# 04_DRIVER.net
KiCad netlist of a schematic drawn in Altium Designer
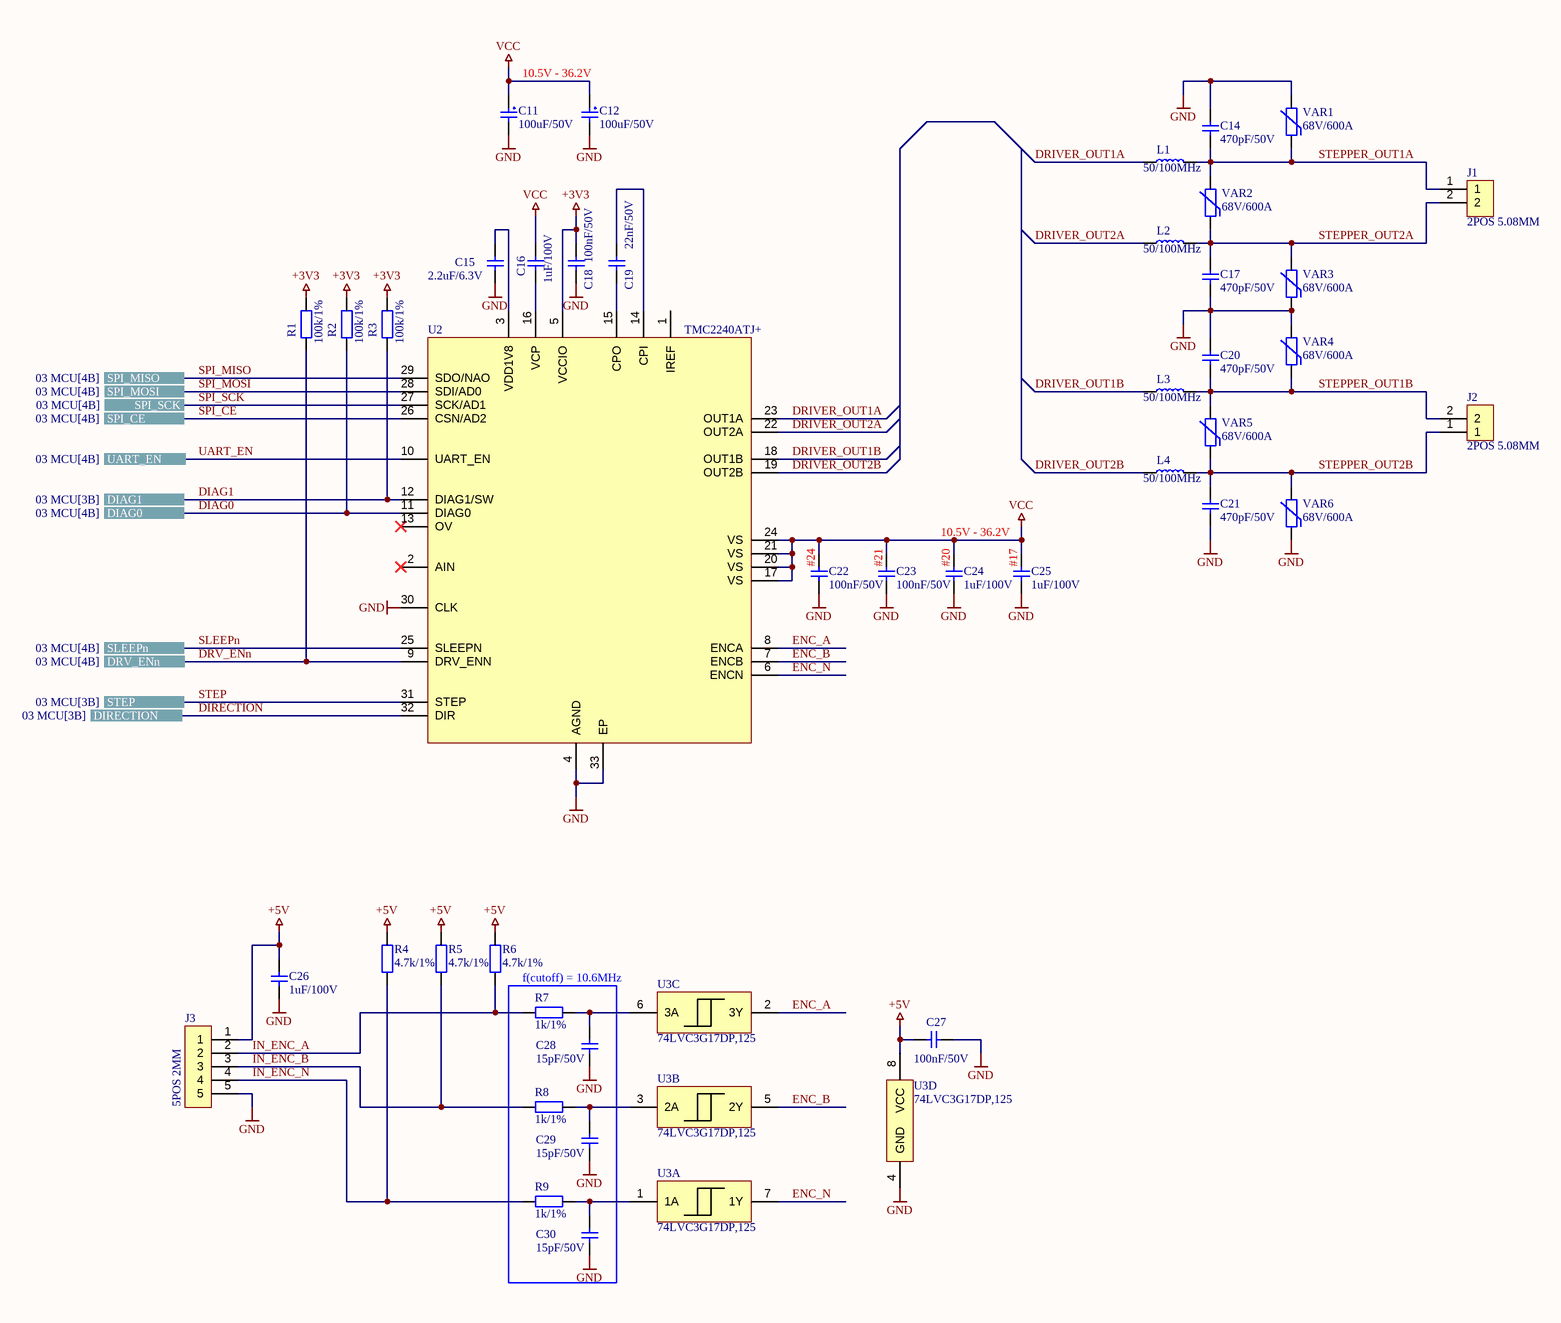
[diagram p0: 04 DRIVER.SchDoc]

(export (version "E")
  (design (tool "Eeschema 10.0.6"))
  (components
    (comp (ref "C11")
      (value "100uF/50V")
      (footprint "A768KS107M1HLAE030")
      (description "100 µF 50 V Aluminum - Polymer Capacitors Radial, Can - SMD 30mOhm 2000 Hrs @ 125°C")
      (fields (field (name "MPN") "A768KS107M1HLAE030"))
      (libsource (lib "Symbol") (part "A768KS107M1HLAE030"))
    )
    (comp (ref "C12")
      (value "100uF/50V")
      (footprint "A768KS107M1HLAE030")
      (description "100 µF 50 V Aluminum - Polymer Capacitors Radial, Can - SMD 30mOhm 2000 Hrs @ 125°C")
      (fields (field (name "MPN") "A768KS107M1HLAE030"))
      (libsource (lib "Symbol") (part "A768KS107M1HLAE030"))
    )
    (comp (ref "C14")
      (value "470pF/50V")
      (footprint "CAPC1005X06M-0402")
      (description "470 pF ±10% 50V Ceramic Capacitor X7R 0402 (1005 Metric)")
      (fields (field (name "MPN") "GRM155R71H471KA01D"))
      (libsource (lib "Symbol") (part "GRM155R71H471KA01D"))
    )
    (comp (ref "C15")
      (value "2.2uF/6.3V")
      (footprint "CAPC1005X06M-0402")
      (description "2.2 µF ±10% 6.3V Ceramic Capacitor X6S 0402 (1005 Metric)")
      (fields (field (name "MPN") "GRM155C80J225KE95D"))
      (libsource (lib "Symbol") (part "GRM155C80J225KE95D"))
    )
    (comp (ref "C16")
      (value "1uF/100V")
      (footprint "CAPC2012X14M")
      (description "1 µF ±10% 100V Ceramic Capacitor X7S 0805 (2012 Metric)")
      (fields (field (name "MPN") "GRM21BC72A105KE01L"))
      (libsource (lib "Symbol") (part "GRM21BC72A105KE01L"))
    )
    (comp (ref "C17")
      (value "470pF/50V")
      (footprint "CAPC1005X06M-0402")
      (description "470 pF ±10% 50V Ceramic Capacitor X7R 0402 (1005 Metric)")
      (fields (field (name "MPN") "GRM155R71H471KA01D"))
      (libsource (lib "Symbol") (part "GRM155R71H471KA01D"))
    )
    (comp (ref "C18")
      (value "100nF/50V")
      (footprint "CAPC1005X06M-0402")
      (description "0.1 µF ±10% 50V Ceramic Capacitor X7R 0402 (1005 Metric)")
      (fields (field (name "MPN") "GRM155R71H104KE14D"))
      (libsource (lib "Symbol") (part "GRM155R71H104KE14D"))
    )
    (comp (ref "C19")
      (value "22nF/50V")
      (footprint "CAPC1005X06M-0402")
      (description "0.022 µF ±10% 50V Ceramic Capacitor X7R 0402 (1005 Metric)")
      (fields (field (name "MPN") "GRM155R71H223KA12D"))
      (libsource (lib "Symbol") (part "GRM155R71H223KA12D"))
    )
    (comp (ref "C20")
      (value "470pF/50V")
      (footprint "CAPC1005X06M-0402")
      (description "470 pF ±10% 50V Ceramic Capacitor X7R 0402 (1005 Metric)")
      (fields (field (name "MPN") "GRM155R71H471KA01D"))
      (libsource (lib "Symbol") (part "GRM155R71H471KA01D"))
    )
    (comp (ref "C21")
      (value "470pF/50V")
      (footprint "CAPC1005X06M-0402")
      (description "470 pF ±10% 50V Ceramic Capacitor X7R 0402 (1005 Metric)")
      (fields (field (name "MPN") "GRM155R71H471KA01D"))
      (libsource (lib "Symbol") (part "GRM155R71H471KA01D"))
    )
    (comp (ref "C22")
      (value "100nF/50V")
      (footprint "CAPC1005X06M-0402")
      (description "0.1 µF ±10% 50V Ceramic Capacitor X7R 0402 (1005 Metric)")
      (fields (field (name "MPN") "GRM155R71H104KE14D"))
      (libsource (lib "Symbol") (part "GRM155R71H104KE14D"))
    )
    (comp (ref "C23")
      (value "100nF/50V")
      (footprint "CAPC1005X06M-0402")
      (description "0.1 µF ±10% 50V Ceramic Capacitor X7R 0402 (1005 Metric)")
      (fields (field (name "MPN") "GRM155R71H104KE14D"))
      (libsource (lib "Symbol") (part "GRM155R71H104KE14D"))
    )
    (comp (ref "C24")
      (value "1uF/100V")
      (footprint "CAPC2012X14M")
      (description "1 µF ±10% 100V Ceramic Capacitor X7S 0805 (2012 Metric)")
      (fields (field (name "MPN") "GRM21BC72A105KE01L"))
      (libsource (lib "Symbol") (part "GRM21BC72A105KE01L"))
    )
    (comp (ref "C25")
      (value "1uF/100V")
      (footprint "CAPC2012X14M")
      (description "1 µF ±10% 100V Ceramic Capacitor X7S 0805 (2012 Metric)")
      (fields (field (name "MPN") "GRM21BC72A105KE01L"))
      (libsource (lib "Symbol") (part "GRM21BC72A105KE01L"))
    )
    (comp (ref "C26")
      (value "1uF/100V")
      (footprint "CAPC2012X14M")
      (description "1 µF ±10% 100V Ceramic Capacitor X7S 0805 (2012 Metric)")
      (fields (field (name "MPN") "GRM21BC72A105KE01L"))
      (libsource (lib "Symbol") (part "GRM21BC72A105KE01L"))
    )
    (comp (ref "C27")
      (value "100nF/50V")
      (footprint "CAPC1005X06M-0402")
      (description "0.1 µF ±10% 50V Ceramic Capacitor X7R 0402 (1005 Metric)")
      (fields (field (name "MPN") "GRM155R71H104KE14D"))
      (libsource (lib "Symbol") (part "GRM155R71H104KE14D"))
    )
    (comp (ref "C28")
      (value "15pF/50V")
      (footprint "CAPC1005X06M-0402")
      (description "15 pF ±5% 50V Ceramic Capacitor C0G, NP0 0402 (1005 Metric)")
      (fields (field (name "MPN") "GRM1555C1H150JA01D"))
      (libsource (lib "Symbol") (part "GRM1555C1H150JA01D"))
    )
    (comp (ref "C29")
      (value "15pF/50V")
      (footprint "CAPC1005X06M-0402")
      (description "15 pF ±5% 50V Ceramic Capacitor C0G, NP0 0402 (1005 Metric)")
      (fields (field (name "MPN") "GRM1555C1H150JA01D"))
      (libsource (lib "Symbol") (part "GRM1555C1H150JA01D"))
    )
    (comp (ref "C30")
      (value "15pF/50V")
      (footprint "CAPC1005X06M-0402")
      (description "15 pF ±5% 50V Ceramic Capacitor C0G, NP0 0402 (1005 Metric)")
      (fields (field (name "MPN") "GRM1555C1H150JA01D"))
      (libsource (lib "Symbol") (part "GRM1555C1H150JA01D"))
    )
    (comp (ref "J1")
      (value "2POS 5.08MM")
      (footprint "282837-2")
      (fields (field (name "MPN") "282834-3"))
      (libsource (lib "") (part "282837-2_1"))
    )
    (comp (ref "J2")
      (value "2POS 5.08MM")
      (footprint "282837-2")
      (fields (field (name "MPN") "282834-3"))
      (libsource (lib "Symbol") (part "282837-2"))
    )
    (comp (ref "J3")
      (value "5POS 2MM")
      (footprint "B5B-PH-K-S")
      (description "Connector Header Through Hole 5 position 0.079\" (2.00mm)")
      (fields (field (name "MPN") "B5B-PH-K-S"))
      (libsource (lib "Symbol") (part "B5B-PH-K-S"))
    )
    (comp (ref "L1")
      (value "50/100MHz")
      (footprint "INDC3200X110-1206")
      (description "50 Ohms 1 Signal Line Ferrite Bead 1206 (3216 Metric) 3A 25mOhm")
      (fields (field (name "MPN") "742792114"))
      (libsource (lib "Symbol") (part "742792114"))
    )
    (comp (ref "L2")
      (value "50/100MHz")
      (footprint "INDC3200X110-1206")
      (description "50 Ohms 1 Signal Line Ferrite Bead 1206 (3216 Metric) 3A 25mOhm")
      (fields (field (name "MPN") "742792114"))
      (libsource (lib "Symbol") (part "742792114"))
    )
    (comp (ref "L3")
      (value "50/100MHz")
      (footprint "INDC3200X110-1206")
      (description "50 Ohms 1 Signal Line Ferrite Bead 1206 (3216 Metric) 3A 25mOhm")
      (fields (field (name "MPN") "742792114"))
      (libsource (lib "Symbol") (part "742792114"))
    )
    (comp (ref "L4")
      (value "50/100MHz")
      (footprint "INDC3200X110-1206")
      (description "50 Ohms 1 Signal Line Ferrite Bead 1206 (3216 Metric) 3A 25mOhm")
      (fields (field (name "MPN") "742792114"))
      (libsource (lib "Symbol") (part "742792114"))
    )
    (comp (ref "R1")
      (value "100k/1%")
      (footprint "RESC1005X04M-0402")
      (description "100 kOhms ±1% 0.063W, 1/16W Chip Resistor 0402 (1005 Metric) Moisture Resistant Thick Film")
      (fields (field (name "MPN") "RC0402FR-07100KL"))
      (libsource (lib "Symbol") (part "RC0402FR-07100KL"))
    )
    (comp (ref "R2")
      (value "100k/1%")
      (footprint "RESC1005X04M-0402")
      (description "100 kOhms ±1% 0.063W, 1/16W Chip Resistor 0402 (1005 Metric) Moisture Resistant Thick Film")
      (fields (field (name "MPN") "RC0402FR-07100KL"))
      (libsource (lib "Symbol") (part "RC0402FR-07100KL"))
    )
    (comp (ref "R3")
      (value "100k/1%")
      (footprint "RESC1005X04M-0402")
      (description "100 kOhms ±1% 0.063W, 1/16W Chip Resistor 0402 (1005 Metric) Moisture Resistant Thick Film")
      (fields (field (name "MPN") "RC0402FR-07100KL"))
      (libsource (lib "Symbol") (part "RC0402FR-07100KL"))
    )
    (comp (ref "R4")
      (value "4.7k/1%")
      (footprint "RESC1005X04M-0402")
      (description "4.7 kOhms ±1% 0.063W, 1/16W Chip Resistor 0402 (1005 Metric) Moisture Resistant Thick Film")
      (fields (field (name "MPN") "RC0402FR-074K7L"))
      (libsource (lib "Symbol") (part "RC0402FR-074K7L"))
    )
    (comp (ref "R5")
      (value "4.7k/1%")
      (footprint "RESC1005X04M-0402")
      (description "4.7 kOhms ±1% 0.063W, 1/16W Chip Resistor 0402 (1005 Metric) Moisture Resistant Thick Film")
      (fields (field (name "MPN") "RC0402FR-074K7L"))
      (libsource (lib "Symbol") (part "RC0402FR-074K7L"))
    )
    (comp (ref "R6")
      (value "4.7k/1%")
      (footprint "RESC1005X04M-0402")
      (description "4.7 kOhms ±1% 0.063W, 1/16W Chip Resistor 0402 (1005 Metric) Moisture Resistant Thick Film")
      (fields (field (name "MPN") "RC0402FR-074K7L"))
      (libsource (lib "Symbol") (part "RC0402FR-074K7L"))
    )
    (comp (ref "R7")
      (value "1k/1%")
      (footprint "RESC1005X04M-0402")
      (description "1 kOhms ±1% 0.063W, 1/16W Chip Resistor 0402 (1005 Metric) Moisture Resistant Thick Film")
      (fields (field (name "MPN") "RC0402FR-071KL"))
      (libsource (lib "Symbol") (part "RC0402FR-071KL"))
    )
    (comp (ref "R8")
      (value "1k/1%")
      (footprint "RESC1005X04M-0402")
      (description "1 kOhms ±1% 0.063W, 1/16W Chip Resistor 0402 (1005 Metric) Moisture Resistant Thick Film")
      (fields (field (name "MPN") "RC0402FR-071KL"))
      (libsource (lib "Symbol") (part "RC0402FR-071KL"))
    )
    (comp (ref "R9")
      (value "1k/1%")
      (footprint "RESC1005X04M-0402")
      (description "1 kOhms ±1% 0.063W, 1/16W Chip Resistor 0402 (1005 Metric) Moisture Resistant Thick Film")
      (fields (field (name "MPN") "RC0402FR-071KL"))
      (libsource (lib "Symbol") (part "RC0402FR-071KL"))
    )
    (comp (ref "U2")
      (value "TMC2240ATJ+")
      (footprint "TQFN32-5mmx5mm")
      (description "Bipolar Motor Driver Power MOSFET SPI, UART 32-TQFN-EP (5x5)")
      (libsource (lib "Symbol") (part "TMC2240ATJ+"))
    )
    (comp (ref "U3")
      (value "74LVC3G17DP,125")
      (footprint "TSOP65P400X110-8N")
      (description "Buffer, Non-Inverting 3 Element 1 Bit per Element Push-Pull Output 8-TSSOP")
      (libsource (lib "Symbol") (part "74LVC3G17DP,125"))
    )
    (comp (ref "VAR1")
      (value "68V/600A")
      (footprint "VARA4732X16N")
      (description "68 V 600 A Varistor 1 Circuit Surface Mount, MLCV 1812 (4532 Metric)")
      (fields (field (name "MPN") "ZV40K1812601NIR1"))
      (libsource (lib "Symbol") (part "ZV40K1812601NIR1"))
    )
    (comp (ref "VAR2")
      (value "68V/600A")
      (footprint "VARA4732X16N")
      (description "68 V 600 A Varistor 1 Circuit Surface Mount, MLCV 1812 (4532 Metric)")
      (fields (field (name "MPN") "ZV40K1812601NIR1"))
      (libsource (lib "Symbol") (part "ZV40K1812601NIR1"))
    )
    (comp (ref "VAR3")
      (value "68V/600A")
      (footprint "VARA4732X16N")
      (description "68 V 600 A Varistor 1 Circuit Surface Mount, MLCV 1812 (4532 Metric)")
      (fields (field (name "MPN") "ZV40K1812601NIR1"))
      (libsource (lib "Symbol") (part "ZV40K1812601NIR1"))
    )
    (comp (ref "VAR4")
      (value "68V/600A")
      (footprint "VARA4732X16N")
      (description "68 V 600 A Varistor 1 Circuit Surface Mount, MLCV 1812 (4532 Metric)")
      (fields (field (name "MPN") "ZV40K1812601NIR1"))
      (libsource (lib "Symbol") (part "ZV40K1812601NIR1"))
    )
    (comp (ref "VAR5")
      (value "68V/600A")
      (footprint "VARA4732X16N")
      (description "68 V 600 A Varistor 1 Circuit Surface Mount, MLCV 1812 (4532 Metric)")
      (fields (field (name "MPN") "ZV40K1812601NIR1"))
      (libsource (lib "Symbol") (part "ZV40K1812601NIR1"))
    )
    (comp (ref "VAR6")
      (value "68V/600A")
      (footprint "VARA4732X16N")
      (description "68 V 600 A Varistor 1 Circuit Surface Mount, MLCV 1812 (4532 Metric)")
      (fields (field (name "MPN") "ZV40K1812601NIR1"))
      (libsource (lib "Symbol") (part "ZV40K1812601NIR1"))
    )
  )
  (nets
    (net (code "1") (name "+3V3") (class "Default")
      (node (ref "C18") (pin "2") (pinfunction "2_2") (pintype "passive"))
      (node (ref "R1") (pin "2") (pinfunction "2_2") (pintype "passive"))
      (node (ref "R2") (pin "2") (pinfunction "2_2") (pintype "passive"))
      (node (ref "R3") (pin "2") (pinfunction "2_2") (pintype "passive"))
      (node (ref "U2") (pin "5") (pinfunction "VCCIO_5") (pintype "power_in"))
    )
    (net (code "2") (name "+5V") (class "Default")
      (node (ref "C26") (pin "2") (pinfunction "2_2") (pintype "passive"))
      (node (ref "C27") (pin "1") (pinfunction "1_1") (pintype "passive"))
      (node (ref "J3") (pin "1") (pinfunction "1_1") (pintype "passive"))
      (node (ref "R4") (pin "2") (pinfunction "2_2") (pintype "passive"))
      (node (ref "R5") (pin "2") (pinfunction "2_2") (pintype "passive"))
      (node (ref "R6") (pin "2") (pinfunction "2_2") (pintype "passive"))
      (node (ref "U3") (pin "8") (pinfunction "VCC_8") (pintype "passive"))
    )
    (net (code "3") (name "/DIAG0") (class "Default")
      (node (ref "R2") (pin "1") (pinfunction "1_1") (pintype "passive"))
      (node (ref "U2") (pin "11") (pinfunction "DIAG0_11") (pintype "passive"))
    )
    (net (code "4") (name "/DIAG1") (class "Default")
      (node (ref "R3") (pin "1") (pinfunction "1_1") (pintype "passive"))
      (node (ref "U2") (pin "12") (pinfunction "DIAG1/SW_12") (pintype "passive"))
    )
    (net (code "5") (name "/DIRECTION") (class "Default")
      (node (ref "U2") (pin "32") (pinfunction "DIR_32") (pintype "passive"))
    )
    (net (code "6") (name "/DRIVER_OUT1A") (class "Default")
      (node (ref "L1") (pin "1") (pinfunction "1_1") (pintype "passive"))
      (node (ref "U2") (pin "23") (pinfunction "OUT1A_23") (pintype "passive"))
    )
    (net (code "7") (name "/DRIVER_OUT1B") (class "Default")
      (node (ref "L3") (pin "1") (pinfunction "1_1") (pintype "passive"))
      (node (ref "U2") (pin "18") (pinfunction "OUT1B_18") (pintype "passive"))
    )
    (net (code "8") (name "/DRIVER_OUT2A") (class "Default")
      (node (ref "L2") (pin "1") (pinfunction "1_1") (pintype "passive"))
      (node (ref "U2") (pin "22") (pinfunction "OUT2A_22") (pintype "passive"))
    )
    (net (code "9") (name "/DRIVER_OUT2B") (class "Default")
      (node (ref "L4") (pin "1") (pinfunction "1_1") (pintype "passive"))
      (node (ref "U2") (pin "19") (pinfunction "OUT2B_19") (pintype "passive"))
    )
    (net (code "10") (name "/DRV_ENn") (class "Default")
      (node (ref "R1") (pin "1") (pinfunction "1_1") (pintype "passive"))
      (node (ref "U2") (pin "9") (pinfunction "DRV_ENN_9") (pintype "passive"))
    )
    (net (code "11") (name "/ENC_A") (class "Default")
      (node (ref "U2") (pin "8") (pinfunction "ENCA_8") (pintype "passive"))
      (node (ref "U3") (pin "2") (pinfunction "3Y_2") (pintype "passive"))
    )
    (net (code "12") (name "/ENC_B") (class "Default")
      (node (ref "U2") (pin "7") (pinfunction "ENCB_7") (pintype "passive"))
      (node (ref "U3") (pin "5") (pinfunction "2Y_5") (pintype "passive"))
    )
    (net (code "13") (name "/ENC_N") (class "Default")
      (node (ref "U2") (pin "6") (pinfunction "ENCN_6") (pintype "passive"))
      (node (ref "U3") (pin "7") (pinfunction "1Y_7") (pintype "passive"))
    )
    (net (code "14") (name "/IN_ENC_A") (class "Default")
      (node (ref "J3") (pin "2") (pinfunction "2_2") (pintype "passive"))
      (node (ref "R6") (pin "1") (pinfunction "1_1") (pintype "passive"))
      (node (ref "R7") (pin "1") (pinfunction "1_1") (pintype "passive"))
    )
    (net (code "15") (name "/IN_ENC_B") (class "Default")
      (node (ref "J3") (pin "3") (pinfunction "3_3") (pintype "passive"))
      (node (ref "R5") (pin "1") (pinfunction "1_1") (pintype "passive"))
      (node (ref "R8") (pin "1") (pinfunction "1_1") (pintype "passive"))
    )
    (net (code "16") (name "/IN_ENC_N") (class "Default")
      (node (ref "J3") (pin "4") (pinfunction "4_4") (pintype "passive"))
      (node (ref "R4") (pin "1") (pinfunction "1_1") (pintype "passive"))
      (node (ref "R9") (pin "1") (pinfunction "1_1") (pintype "passive"))
    )
    (net (code "17") (name "/SLEEPn") (class "Default")
      (node (ref "U2") (pin "25") (pinfunction "SLEEPN_25") (pintype "passive"))
    )
    (net (code "18") (name "/SPI_CE") (class "Default")
      (node (ref "U2") (pin "26") (pinfunction "CSN/AD2_26") (pintype "passive"))
    )
    (net (code "19") (name "/SPI_MISO") (class "Default")
      (node (ref "U2") (pin "29") (pinfunction "SDO/NAO_29") (pintype "passive"))
    )
    (net (code "20") (name "/SPI_MOSI") (class "Default")
      (node (ref "U2") (pin "28") (pinfunction "SDI/AD0_28") (pintype "passive"))
    )
    (net (code "21") (name "/SPI_SCK") (class "Default")
      (node (ref "U2") (pin "27") (pinfunction "SCK/AD1_27") (pintype "passive"))
    )
    (net (code "22") (name "/STEP") (class "Default")
      (node (ref "U2") (pin "31") (pinfunction "STEP_31") (pintype "passive"))
    )
    (net (code "23") (name "/STEPPER_OUT1A") (class "Default")
      (node (ref "C14") (pin "2") (pinfunction "2_2") (pintype "passive"))
      (node (ref "J1") (pin "1") (pinfunction "1_1") (pintype "passive"))
      (node (ref "L1") (pin "2") (pinfunction "2_2") (pintype "passive"))
      (node (ref "VAR1") (pin "1") (pinfunction "1_1") (pintype "passive"))
      (node (ref "VAR2") (pin "2") (pinfunction "2_2") (pintype "passive"))
    )
    (net (code "24") (name "/STEPPER_OUT1B") (class "Default")
      (node (ref "C20") (pin "2") (pinfunction "2_2") (pintype "passive"))
      (node (ref "J2") (pin "2") (pinfunction "2_2") (pintype "passive"))
      (node (ref "L3") (pin "2") (pinfunction "2_2") (pintype "passive"))
      (node (ref "VAR4") (pin "1") (pinfunction "1_1") (pintype "passive"))
      (node (ref "VAR5") (pin "2") (pinfunction "2_2") (pintype "passive"))
    )
    (net (code "25") (name "/STEPPER_OUT2A") (class "Default")
      (node (ref "C17") (pin "1") (pinfunction "1_1") (pintype "passive"))
      (node (ref "J1") (pin "2") (pinfunction "2_2") (pintype "passive"))
      (node (ref "L2") (pin "2") (pinfunction "2_2") (pintype "passive"))
      (node (ref "VAR2") (pin "1") (pinfunction "1_1") (pintype "passive"))
      (node (ref "VAR3") (pin "2") (pinfunction "2_2") (pintype "passive"))
    )
    (net (code "26") (name "/STEPPER_OUT2B") (class "Default")
      (node (ref "C21") (pin "1") (pinfunction "1_1") (pintype "passive"))
      (node (ref "J2") (pin "1") (pinfunction "1_1") (pintype "passive"))
      (node (ref "L4") (pin "2") (pinfunction "2_2") (pintype "passive"))
      (node (ref "VAR5") (pin "1") (pinfunction "1_1") (pintype "passive"))
      (node (ref "VAR6") (pin "2") (pinfunction "2_2") (pintype "passive"))
    )
    (net (code "27") (name "/UART_EN") (class "Default")
      (node (ref "U2") (pin "10") (pinfunction "UART_EN_10") (pintype "passive"))
    )
    (net (code "28") (name "GND") (class "Default")
      (node (ref "C11") (pin "2") (pinfunction "2_2") (pintype "passive"))
      (node (ref "C12") (pin "2") (pinfunction "2_2") (pintype "passive"))
      (node (ref "C14") (pin "1") (pinfunction "1_1") (pintype "passive"))
      (node (ref "C15") (pin "1") (pinfunction "1_1") (pintype "passive"))
      (node (ref "C17") (pin "2") (pinfunction "2_2") (pintype "passive"))
      (node (ref "C18") (pin "1") (pinfunction "1_1") (pintype "passive"))
      (node (ref "C20") (pin "1") (pinfunction "1_1") (pintype "passive"))
      (node (ref "C21") (pin "2") (pinfunction "2_2") (pintype "passive"))
      (node (ref "C22") (pin "1") (pinfunction "1_1") (pintype "passive"))
      (node (ref "C23") (pin "1") (pinfunction "1_1") (pintype "passive"))
      (node (ref "C24") (pin "1") (pinfunction "1_1") (pintype "passive"))
      (node (ref "C25") (pin "1") (pinfunction "1_1") (pintype "passive"))
      (node (ref "C26") (pin "1") (pinfunction "1_1") (pintype "passive"))
      (node (ref "C27") (pin "2") (pinfunction "2_2") (pintype "passive"))
      (node (ref "C28") (pin "1") (pinfunction "1_1") (pintype "passive"))
      (node (ref "C29") (pin "1") (pinfunction "1_1") (pintype "passive"))
      (node (ref "C30") (pin "1") (pinfunction "1_1") (pintype "passive"))
      (node (ref "J3") (pin "5") (pinfunction "5_5") (pintype "passive"))
      (node (ref "U2") (pin "30") (pinfunction "CLK_30") (pintype "passive"))
      (node (ref "U2") (pin "33") (pinfunction "EP_33") (pintype "passive"))
      (node (ref "U2") (pin "4") (pinfunction "AGND_4") (pintype "power_in"))
      (node (ref "U3") (pin "4") (pinfunction "GND_4") (pintype "passive"))
      (node (ref "VAR1") (pin "2") (pinfunction "2_2") (pintype "passive"))
      (node (ref "VAR3") (pin "1") (pinfunction "1_1") (pintype "passive"))
      (node (ref "VAR4") (pin "2") (pinfunction "2_2") (pintype "passive"))
      (node (ref "VAR6") (pin "1") (pinfunction "1_1") (pintype "passive"))
    )
    (net (code "29") (name "Net-(U2-CPI)") (class "Default")
      (node (ref "C19") (pin "2") (pinfunction "2_2") (pintype "passive"))
      (node (ref "U2") (pin "14") (pinfunction "CPI_14") (pintype "passive"))
    )
    (net (code "30") (name "Net-(U2-CPO)") (class "Default")
      (node (ref "C19") (pin "1") (pinfunction "1_1") (pintype "passive"))
      (node (ref "U2") (pin "15") (pinfunction "CPO_15") (pintype "passive"))
    )
    (net (code "31") (name "Net-(U2-VCP)") (class "Default")
      (node (ref "C16") (pin "1") (pinfunction "1_1") (pintype "passive"))
      (node (ref "U2") (pin "16") (pinfunction "VCP_16") (pintype "power_in"))
    )
    (net (code "32") (name "Net-(U2-VDD1V8)") (class "Default")
      (node (ref "C15") (pin "2") (pinfunction "2_2") (pintype "passive"))
      (node (ref "U2") (pin "3") (pinfunction "VDD1V8_3") (pintype "power_in"))
    )
    (net (code "33") (name "Net-(U3A-1A)") (class "Default")
      (node (ref "C30") (pin "2") (pinfunction "2_2") (pintype "passive"))
      (node (ref "R9") (pin "2") (pinfunction "2_2") (pintype "passive"))
      (node (ref "U3") (pin "1") (pinfunction "1A_1") (pintype "passive"))
    )
    (net (code "34") (name "Net-(U3B-2A)") (class "Default")
      (node (ref "C29") (pin "2") (pinfunction "2_2") (pintype "passive"))
      (node (ref "R8") (pin "2") (pinfunction "2_2") (pintype "passive"))
      (node (ref "U3") (pin "3") (pinfunction "2A_3") (pintype "passive"))
    )
    (net (code "35") (name "Net-(U3C-3A)") (class "Default")
      (node (ref "C28") (pin "2") (pinfunction "2_2") (pintype "passive"))
      (node (ref "R7") (pin "2") (pinfunction "2_2") (pintype "passive"))
      (node (ref "U3") (pin "6") (pinfunction "3A_6") (pintype "passive"))
    )
    (net (code "36") (name "VCC") (class "Default")
      (node (ref "C11") (pin "1") (pinfunction "1_1") (pintype "passive"))
      (node (ref "C12") (pin "1") (pinfunction "1_1") (pintype "passive"))
      (node (ref "C16") (pin "2") (pinfunction "2_2") (pintype "passive"))
      (node (ref "C22") (pin "2") (pinfunction "2_2") (pintype "passive"))
      (node (ref "C23") (pin "2") (pinfunction "2_2") (pintype "passive"))
      (node (ref "C24") (pin "2") (pinfunction "2_2") (pintype "passive"))
      (node (ref "C25") (pin "2") (pinfunction "2_2") (pintype "passive"))
      (node (ref "U2") (pin "17") (pinfunction "VS_17") (pintype "power_in"))
      (node (ref "U2") (pin "20") (pinfunction "VS_20") (pintype "power_in"))
      (node (ref "U2") (pin "21") (pinfunction "VS_21") (pintype "power_in"))
      (node (ref "U2") (pin "24") (pinfunction "VS_24") (pintype "power_in"))
    )
    (net (code "37") (name "unconnected-(U2-AIN-Pad2)") (class "Default")
      (node (ref "U2") (pin "2") (pinfunction "AIN_2") (pintype "passive+no_connect"))
    )
    (net (code "38") (name "unconnected-(U2-IREF-Pad1)") (class "Default")
      (node (ref "U2") (pin "1") (pinfunction "IREF_1") (pintype "passive"))
    )
    (net (code "39") (name "unconnected-(U2-OV-Pad13)") (class "Default")
      (node (ref "U2") (pin "13") (pinfunction "OV_13") (pintype "passive+no_connect"))
    )
  )
)
